# Dash_V2.net
KiCad netlist of a schematic drawn in EAGLE
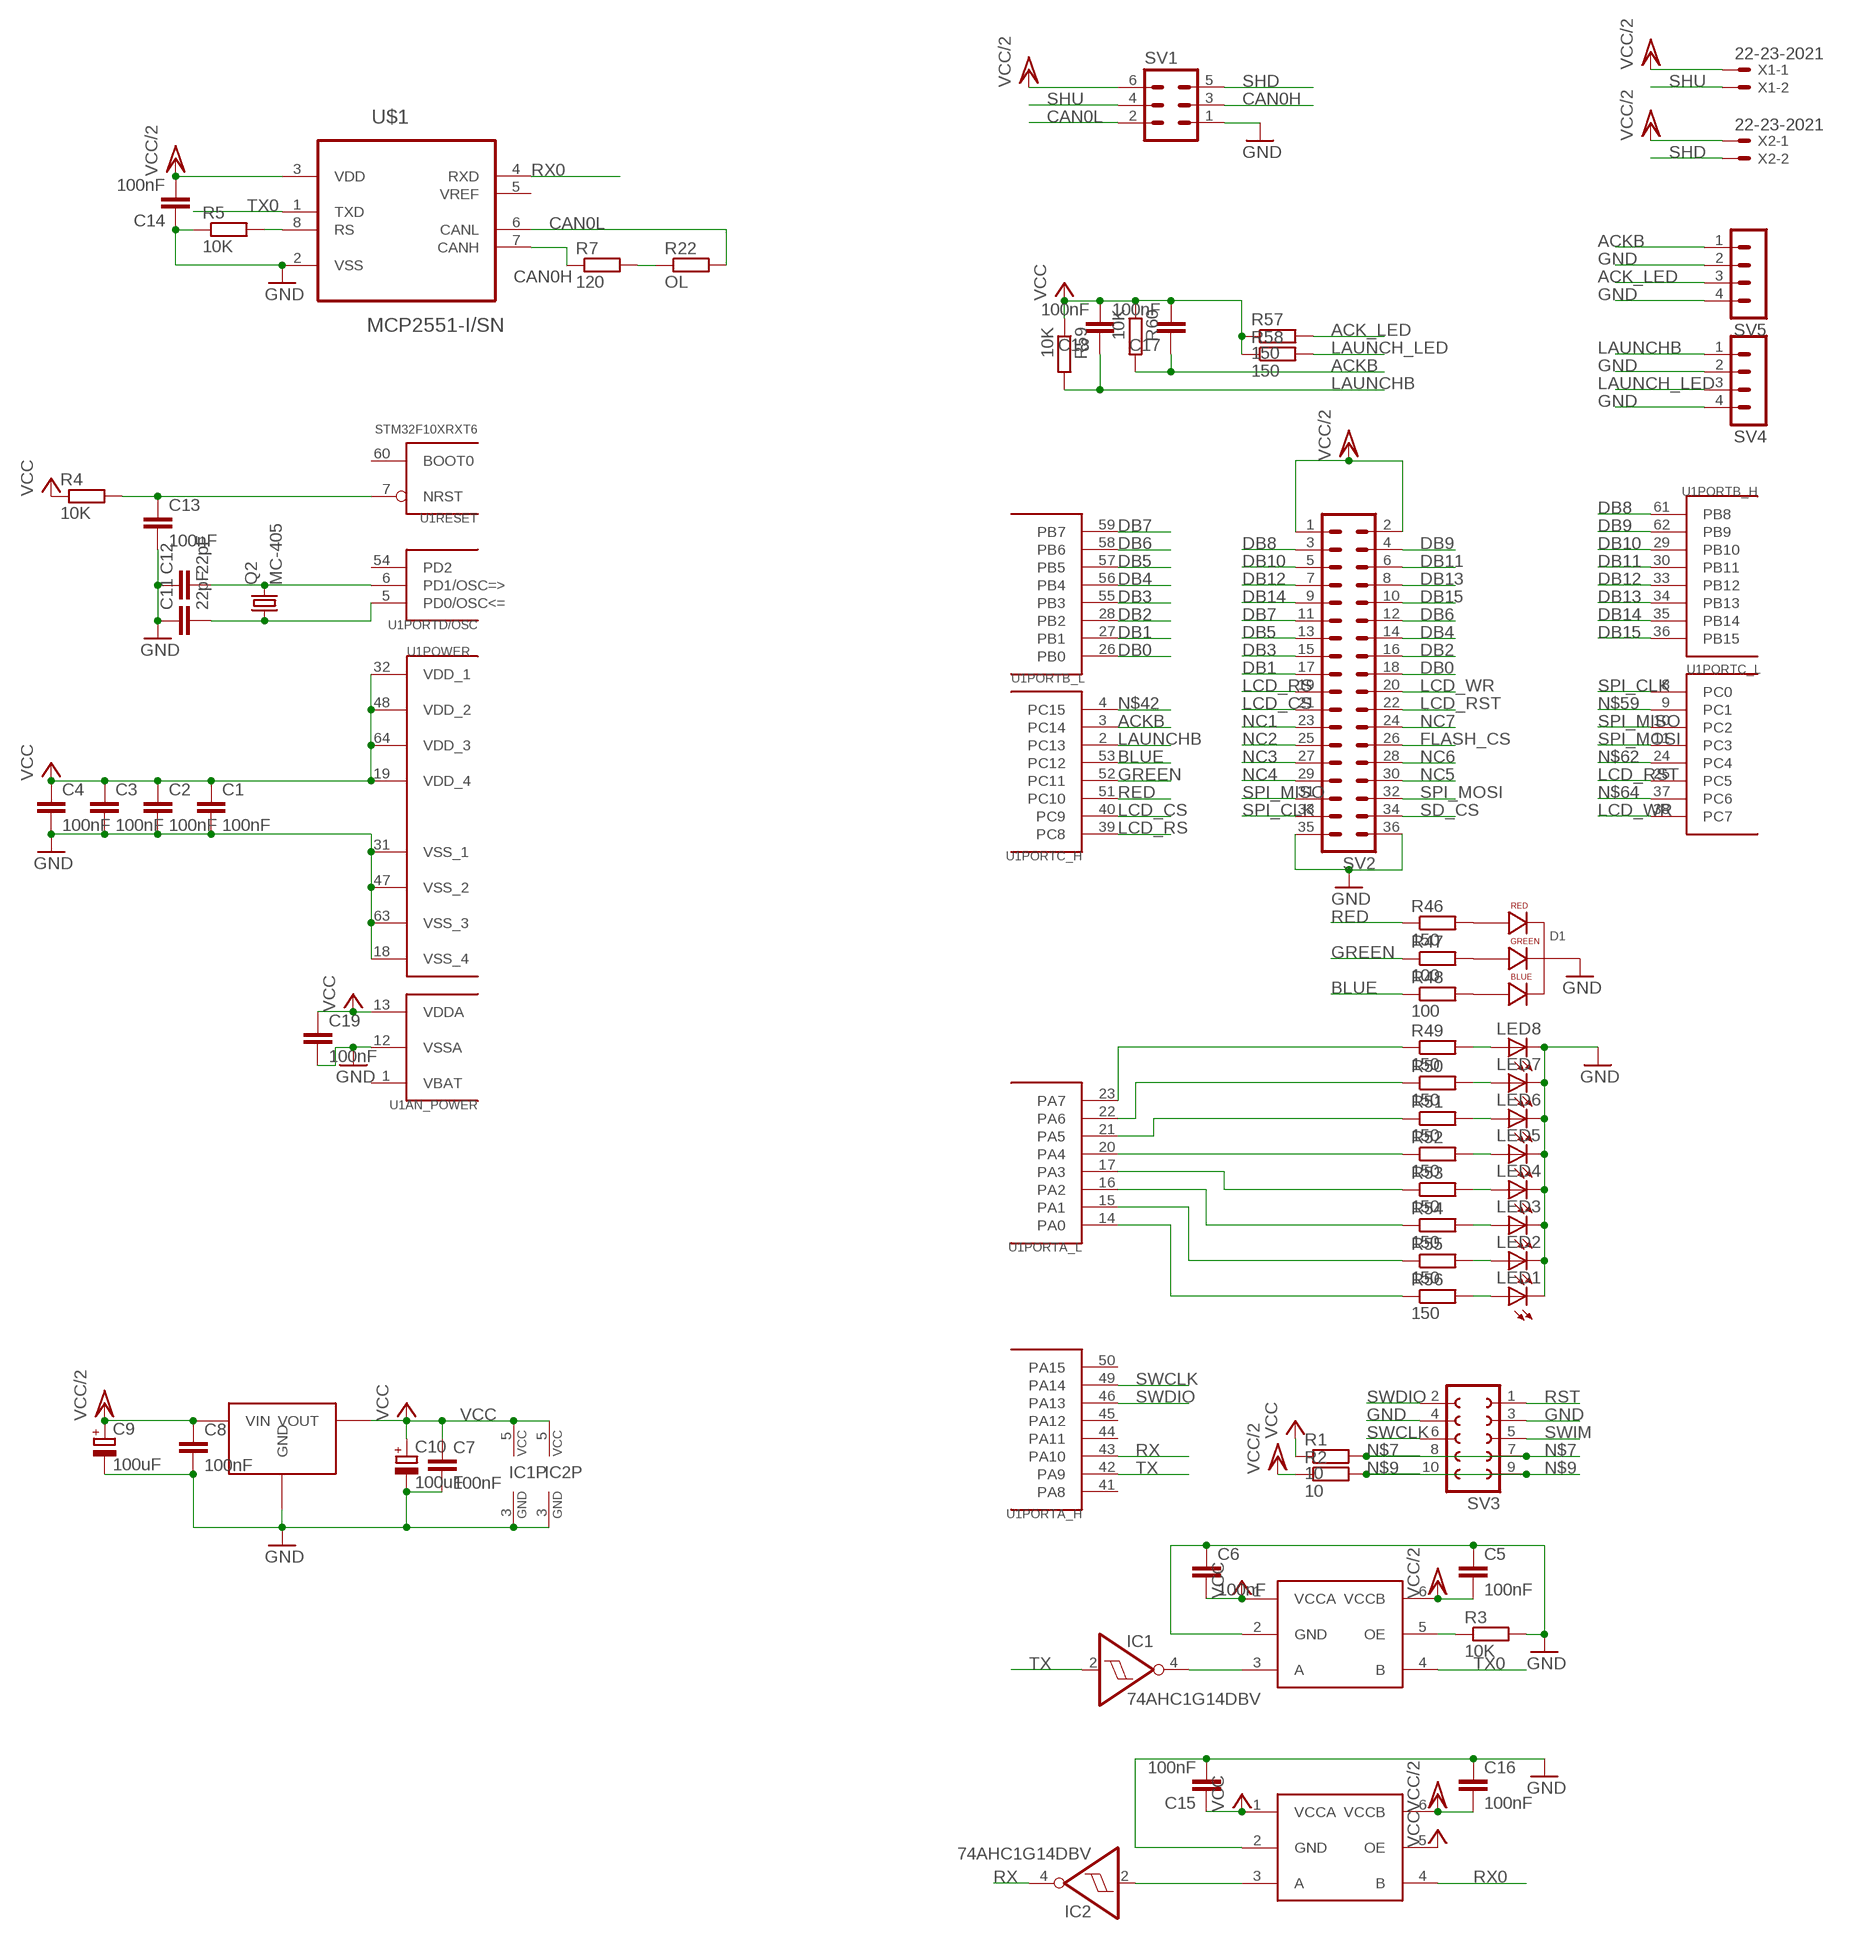
[diagram p0: schematic, sheet 1]

(export (version "E")
  (design (tool "Eeschema 10.0.6"))
  (components
    (comp (ref "C1")
      (value "100nF")
      (footprint "eagle-import:C0805")
      (libsource (lib "eagle-import") (part "C-EUC0805"))
    )
    (comp (ref "C2")
      (value "100nF")
      (footprint "eagle-import:C0805")
      (libsource (lib "eagle-import") (part "C-EUC0805"))
    )
    (comp (ref "C3")
      (value "100nF")
      (footprint "eagle-import:C0805")
      (libsource (lib "eagle-import") (part "C-EUC0805"))
    )
    (comp (ref "C4")
      (value "100nF")
      (footprint "eagle-import:C0805")
      (libsource (lib "eagle-import") (part "C-EUC0805"))
    )
    (comp (ref "C5")
      (value "100nF")
      (footprint "eagle-import:C0805")
      (libsource (lib "eagle-import") (part "C-EUC0805"))
    )
    (comp (ref "C6")
      (value "100nF")
      (footprint "eagle-import:C0805")
      (libsource (lib "eagle-import") (part "C-EUC0805"))
    )
    (comp (ref "C7")
      (value "100nF")
      (footprint "eagle-import:C0805")
      (libsource (lib "eagle-import") (part "C-EUC0805"))
    )
    (comp (ref "C8")
      (value "100nF")
      (footprint "eagle-import:C0805")
      (libsource (lib "eagle-import") (part "C-EUC0805"))
    )
    (comp (ref "C9")
      (value "100uF")
      (footprint "eagle-import:153CLV-0605")
      (libsource (lib "eagle-import") (part "CPOL-EU153CLV-0605"))
    )
    (comp (ref "C10")
      (value "100uF")
      (footprint "eagle-import:153CLV-0605")
      (libsource (lib "eagle-import") (part "CPOL-EU153CLV-0605"))
    )
    (comp (ref "C11")
      (value "22pF")
      (footprint "eagle-import:C0805")
      (libsource (lib "eagle-import") (part "C-EUC0805"))
    )
    (comp (ref "C12")
      (value "22pF")
      (footprint "eagle-import:C0805")
      (libsource (lib "eagle-import") (part "C-EUC0805"))
    )
    (comp (ref "C13")
      (value "100nF")
      (footprint "eagle-import:C0805")
      (libsource (lib "eagle-import") (part "C-EUC0805"))
    )
    (comp (ref "C14")
      (value "100nF")
      (footprint "eagle-import:C0805")
      (libsource (lib "eagle-import") (part "C-EUC0805"))
    )
    (comp (ref "C15")
      (value "100nF")
      (footprint "eagle-import:C0805")
      (libsource (lib "eagle-import") (part "C-EUC0805"))
    )
    (comp (ref "C16")
      (value "100nF")
      (footprint "eagle-import:C0805")
      (libsource (lib "eagle-import") (part "C-EUC0805"))
    )
    (comp (ref "C17")
      (value "100nF")
      (footprint "eagle-import:C0805")
      (libsource (lib "eagle-import") (part "C-EUC0805"))
    )
    (comp (ref "C18")
      (value "100nF")
      (footprint "eagle-import:C0805")
      (libsource (lib "eagle-import") (part "C-EUC0805"))
    )
    (comp (ref "C19")
      (value "100nF")
      (footprint "eagle-import:C0805")
      (libsource (lib "eagle-import") (part "C-EUC0805"))
    )
    (comp (ref "D1")
      (value "LED-RGB-CC-THRUDIFFUSE")
      (footprint "eagle-import:LED-RGB-THRU")
      (libsource (lib "eagle-import") (part "LED-RGB-CC-THRUDIFFUSE"))
    )
    (comp (ref "IC1")
      (value "74AHC1G14DBV")
      (footprint "eagle-import:SOT23-5")
      (fields (field (name "FARNELL") "1893832"))
      (libsource (lib "eagle-import") (part "741G14DBVAHC"))
    )
    (comp (ref "IC2")
      (value "74AHC1G14DBV")
      (footprint "eagle-import:SOT23-5")
      (fields (field (name "FARNELL") "1893832"))
      (libsource (lib "eagle-import") (part "741G14DBVAHC"))
    )
    (comp (ref "LED1")
      (value "LED5MM")
      (footprint "eagle-import:LED5MM")
      (libsource (lib "eagle-import") (part "LED5MM"))
    )
    (comp (ref "LED2")
      (value "LED5MM")
      (footprint "eagle-import:LED5MM")
      (libsource (lib "eagle-import") (part "LED5MM"))
    )
    (comp (ref "LED3")
      (value "LED5MM")
      (footprint "eagle-import:LED5MM")
      (libsource (lib "eagle-import") (part "LED5MM"))
    )
    (comp (ref "LED4")
      (value "LED5MM")
      (footprint "eagle-import:LED5MM")
      (libsource (lib "eagle-import") (part "LED5MM"))
    )
    (comp (ref "LED5")
      (value "LED5MM")
      (footprint "eagle-import:LED5MM")
      (libsource (lib "eagle-import") (part "LED5MM"))
    )
    (comp (ref "LED6")
      (value "LED5MM")
      (footprint "eagle-import:LED5MM")
      (libsource (lib "eagle-import") (part "LED5MM"))
    )
    (comp (ref "LED7")
      (value "LED5MM")
      (footprint "eagle-import:LED5MM")
      (libsource (lib "eagle-import") (part "LED5MM"))
    )
    (comp (ref "LED8")
      (value "LED5MM")
      (footprint "eagle-import:LED5MM")
      (libsource (lib "eagle-import") (part "LED5MM"))
    )
    (comp (ref "Q2")
      (value "MC-405")
      (footprint "eagle-import:MC-405")
      (fields (field (name "OC_FARNELL") "2101329"))
      (libsource (lib "eagle-import") (part "MC-405"))
    )
    (comp (ref "R1")
      (value "10")
      (footprint "eagle-import:R0805")
      (libsource (lib "eagle-import") (part "R-EU_R0805"))
    )
    (comp (ref "R2")
      (value "10")
      (footprint "eagle-import:R0805")
      (libsource (lib "eagle-import") (part "R-EU_R0805"))
    )
    (comp (ref "R3")
      (value "10K")
      (footprint "eagle-import:R1206")
      (libsource (lib "eagle-import") (part "R-EU_R1206"))
    )
    (comp (ref "R4")
      (value "10K")
      (footprint "eagle-import:R0805")
      (libsource (lib "eagle-import") (part "R-EU_R0805"))
    )
    (comp (ref "R5")
      (value "10K")
      (footprint "eagle-import:R0805")
      (libsource (lib "eagle-import") (part "R-EU_R0805"))
    )
    (comp (ref "R7")
      (value "120")
      (footprint "eagle-import:R0805")
      (libsource (lib "eagle-import") (part "R-EU_R0805"))
    )
    (comp (ref "R22")
      (value "OL")
      (footprint "eagle-import:R0805")
      (libsource (lib "eagle-import") (part "R-EU_R0805"))
    )
    (comp (ref "R46")
      (value "150")
      (footprint "eagle-import:R1206")
      (libsource (lib "eagle-import") (part "R-EU_R1206"))
    )
    (comp (ref "R47")
      (value "100")
      (footprint "eagle-import:R1206")
      (libsource (lib "eagle-import") (part "R-EU_R1206"))
    )
    (comp (ref "R48")
      (value "100")
      (footprint "eagle-import:R1206")
      (libsource (lib "eagle-import") (part "R-EU_R1206"))
    )
    (comp (ref "R49")
      (value "150")
      (footprint "eagle-import:R1206")
      (libsource (lib "eagle-import") (part "R-EU_R1206"))
    )
    (comp (ref "R50")
      (value "150")
      (footprint "eagle-import:R1206")
      (libsource (lib "eagle-import") (part "R-EU_R1206"))
    )
    (comp (ref "R51")
      (value "150")
      (footprint "eagle-import:R1206")
      (libsource (lib "eagle-import") (part "R-EU_R1206"))
    )
    (comp (ref "R52")
      (value "150")
      (footprint "eagle-import:R1206")
      (libsource (lib "eagle-import") (part "R-EU_R1206"))
    )
    (comp (ref "R53")
      (value "150")
      (footprint "eagle-import:R1206")
      (libsource (lib "eagle-import") (part "R-EU_R1206"))
    )
    (comp (ref "R54")
      (value "150")
      (footprint "eagle-import:R1206")
      (libsource (lib "eagle-import") (part "R-EU_R1206"))
    )
    (comp (ref "R55")
      (value "150")
      (footprint "eagle-import:R1206")
      (libsource (lib "eagle-import") (part "R-EU_R1206"))
    )
    (comp (ref "R56")
      (value "150")
      (footprint "eagle-import:R1206")
      (libsource (lib "eagle-import") (part "R-EU_R1206"))
    )
    (comp (ref "R57")
      (value "150")
      (footprint "eagle-import:R1206")
      (libsource (lib "eagle-import") (part "R-EU_R1206"))
    )
    (comp (ref "R58")
      (value "150")
      (footprint "eagle-import:R1206")
      (libsource (lib "eagle-import") (part "R-EU_R1206"))
    )
    (comp (ref "R59")
      (value "10K")
      (footprint "eagle-import:R1206")
      (libsource (lib "eagle-import") (part "R-EU_R1206"))
    )
    (comp (ref "R60")
      (value "10K")
      (footprint "eagle-import:R1206")
      (libsource (lib "eagle-import") (part "R-EU_R1206"))
    )
    (comp (ref "SV1")
      (value "MA03-2")
      (footprint "eagle-import:MA03-2")
      (libsource (lib "eagle-import") (part "MA03-2"))
    )
    (comp (ref "SV2")
      (value "MA18-2")
      (footprint "eagle-import:MA18-2")
      (libsource (lib "eagle-import") (part "MA18-2"))
    )
    (comp (ref "SV3")
      (value "FE05-2W")
      (footprint "eagle-import:FE05-2W")
      (libsource (lib "eagle-import") (part "FE05-2W"))
    )
    (comp (ref "SV4")
      (value "MA04-1")
      (footprint "eagle-import:MA04-1")
      (libsource (lib "eagle-import") (part "MA04-1"))
    )
    (comp (ref "SV5")
      (value "MA04-1")
      (footprint "eagle-import:MA04-1")
      (libsource (lib "eagle-import") (part "MA04-1"))
    )
    (comp (ref "U$1")
      (value "MCP2551-I/SN")
      (footprint "eagle-import:SOIC127P600X175-8N")
      (libsource (lib "eagle-import") (part "MCP2551-I/SN"))
    )
    (comp (ref "U$2")
      (value "TXB0101")
      (footprint "eagle-import:TSOT23-6_DDC")
      (libsource (lib "eagle-import") (part "TXB0101"))
    )
    (comp (ref "U$3")
      (value "TS2940")
      (footprint "eagle-import:TO-252")
      (libsource (lib "eagle-import") (part "TS2940"))
    )
    (comp (ref "U$4")
      (value "TXB0101")
      (footprint "eagle-import:TSOT23-6_DDC")
      (libsource (lib "eagle-import") (part "TXB0101"))
    )
    (comp (ref "U1")
      (value "STM32F10XRXT6")
      (footprint "eagle-import:TQFP64")
      (libsource (lib "eagle-import") (part "STM32F10XRXT6"))
    )
    (comp (ref "X1")
      (value "22-23-2021")
      (footprint "eagle-import:22-23-2021")
      (fields (field (name "MF") "MOLEX"))
      (libsource (lib "eagle-import") (part "22-23-2021"))
    )
    (comp (ref "X2")
      (value "22-23-2021")
      (footprint "eagle-import:22-23-2021")
      (fields (field (name "MF") "MOLEX"))
      (libsource (lib "eagle-import") (part "22-23-2021"))
    )
  )
  (nets
    (net (code "1") (name "/ACKB") (class "Default")
      (node (ref "C17") (pin "1") (pinfunction "1_1") (pintype "passive"))
      (node (ref "R60") (pin "2") (pinfunction "2_2") (pintype "passive"))
      (node (ref "SV5") (pin "1") (pinfunction "1_1") (pintype "passive"))
      (node (ref "U1") (pin "3") (pinfunction "PC14_3") (pintype "bidirectional"))
    )
    (net (code "2") (name "/ACK_LED") (class "Default")
      (node (ref "R57") (pin "2") (pinfunction "2_2") (pintype "passive"))
      (node (ref "SV5") (pin "3") (pinfunction "3_3") (pintype "passive"))
    )
    (net (code "3") (name "/BLUE") (class "Default")
      (node (ref "R48") (pin "1") (pinfunction "1_1") (pintype "passive"))
      (node (ref "U1") (pin "53") (pinfunction "PC12_53") (pintype "bidirectional"))
    )
    (net (code "4") (name "/CAN0H") (class "Default")
      (node (ref "R7") (pin "1") (pinfunction "1_1") (pintype "passive"))
      (node (ref "SV1") (pin "3") (pinfunction "3_3") (pintype "passive"))
      (node (ref "U$1") (pin "7") (pinfunction "CANH_7") (pintype "bidirectional"))
    )
    (net (code "5") (name "/CAN0L") (class "Default")
      (node (ref "R22") (pin "2") (pinfunction "2_2") (pintype "passive"))
      (node (ref "SV1") (pin "2") (pinfunction "2_2") (pintype "passive"))
      (node (ref "U$1") (pin "6") (pinfunction "CANL_6") (pintype "bidirectional"))
    )
    (net (code "6") (name "/DB0") (class "Default")
      (node (ref "SV2") (pin "18") (pinfunction "18_18") (pintype "passive"))
      (node (ref "U1") (pin "26") (pinfunction "PB0_26") (pintype "bidirectional"))
    )
    (net (code "7") (name "/DB1") (class "Default")
      (node (ref "SV2") (pin "17") (pinfunction "17_17") (pintype "passive"))
      (node (ref "U1") (pin "27") (pinfunction "PB1_27") (pintype "bidirectional"))
    )
    (net (code "8") (name "/DB2") (class "Default")
      (node (ref "SV2") (pin "16") (pinfunction "16_16") (pintype "passive"))
      (node (ref "U1") (pin "28") (pinfunction "PB2_28") (pintype "bidirectional"))
    )
    (net (code "9") (name "/DB3") (class "Default")
      (node (ref "SV2") (pin "15") (pinfunction "15_15") (pintype "passive"))
      (node (ref "U1") (pin "55") (pinfunction "PB3_55") (pintype "bidirectional"))
    )
    (net (code "10") (name "/DB4") (class "Default")
      (node (ref "SV2") (pin "14") (pinfunction "14_14") (pintype "passive"))
      (node (ref "U1") (pin "56") (pinfunction "PB4_56") (pintype "bidirectional"))
    )
    (net (code "11") (name "/DB5") (class "Default")
      (node (ref "SV2") (pin "13") (pinfunction "13_13") (pintype "passive"))
      (node (ref "U1") (pin "57") (pinfunction "PB5_57") (pintype "bidirectional"))
    )
    (net (code "12") (name "/DB6") (class "Default")
      (node (ref "SV2") (pin "12") (pinfunction "12_12") (pintype "passive"))
      (node (ref "U1") (pin "58") (pinfunction "PB6_58") (pintype "bidirectional"))
    )
    (net (code "13") (name "/DB7") (class "Default")
      (node (ref "SV2") (pin "11") (pinfunction "11_11") (pintype "passive"))
      (node (ref "U1") (pin "59") (pinfunction "PB7_59") (pintype "bidirectional"))
    )
    (net (code "14") (name "/DB8") (class "Default")
      (node (ref "SV2") (pin "3") (pinfunction "3_3") (pintype "passive"))
      (node (ref "U1") (pin "61") (pinfunction "PB8_61") (pintype "bidirectional"))
    )
    (net (code "15") (name "/DB9") (class "Default")
      (node (ref "SV2") (pin "4") (pinfunction "4_4") (pintype "passive"))
      (node (ref "U1") (pin "62") (pinfunction "PB9_62") (pintype "bidirectional"))
    )
    (net (code "16") (name "/DB10") (class "Default")
      (node (ref "SV2") (pin "5") (pinfunction "5_5") (pintype "passive"))
      (node (ref "U1") (pin "29") (pinfunction "PB10_29") (pintype "bidirectional"))
    )
    (net (code "17") (name "/DB11") (class "Default")
      (node (ref "SV2") (pin "6") (pinfunction "6_6") (pintype "passive"))
      (node (ref "U1") (pin "30") (pinfunction "PB11_30") (pintype "bidirectional"))
    )
    (net (code "18") (name "/DB12") (class "Default")
      (node (ref "SV2") (pin "7") (pinfunction "7_7") (pintype "passive"))
      (node (ref "U1") (pin "33") (pinfunction "PB12_33") (pintype "bidirectional"))
    )
    (net (code "19") (name "/DB13") (class "Default")
      (node (ref "SV2") (pin "8") (pinfunction "8_8") (pintype "passive"))
      (node (ref "U1") (pin "34") (pinfunction "PB13_34") (pintype "bidirectional"))
    )
    (net (code "20") (name "/DB14") (class "Default")
      (node (ref "SV2") (pin "9") (pinfunction "9_9") (pintype "passive"))
      (node (ref "U1") (pin "35") (pinfunction "PB14_35") (pintype "bidirectional"))
    )
    (net (code "21") (name "/DB15") (class "Default")
      (node (ref "SV2") (pin "10") (pinfunction "10_10") (pintype "passive"))
      (node (ref "U1") (pin "36") (pinfunction "PB15_36") (pintype "bidirectional"))
    )
    (net (code "22") (name "/FLASH_CS") (class "Default")
      (node (ref "SV2") (pin "26") (pinfunction "26_26") (pintype "passive"))
    )
    (net (code "23") (name "/GREEN") (class "Default")
      (node (ref "R47") (pin "1") (pinfunction "1_1") (pintype "passive"))
      (node (ref "U1") (pin "52") (pinfunction "PC11_52") (pintype "bidirectional"))
    )
    (net (code "24") (name "/LAUNCHB") (class "Default")
      (node (ref "C18") (pin "1") (pinfunction "1_1") (pintype "passive"))
      (node (ref "R59") (pin "2") (pinfunction "2_2") (pintype "passive"))
      (node (ref "SV4") (pin "1") (pinfunction "1_1") (pintype "passive"))
      (node (ref "U1") (pin "2") (pinfunction "PC13_2") (pintype "bidirectional"))
    )
    (net (code "25") (name "/LAUNCH_LED") (class "Default")
      (node (ref "R58") (pin "2") (pinfunction "2_2") (pintype "passive"))
      (node (ref "SV4") (pin "3") (pinfunction "3_3") (pintype "passive"))
    )
    (net (code "26") (name "/LCD_CS") (class "Default")
      (node (ref "SV2") (pin "21") (pinfunction "21_21") (pintype "passive"))
      (node (ref "U1") (pin "40") (pinfunction "PC9_40") (pintype "bidirectional"))
    )
    (net (code "27") (name "/LCD_RS") (class "Default")
      (node (ref "SV2") (pin "19") (pinfunction "19_19") (pintype "passive"))
      (node (ref "U1") (pin "39") (pinfunction "PC8_39") (pintype "bidirectional"))
    )
    (net (code "28") (name "/LCD_RST") (class "Default")
      (node (ref "SV2") (pin "22") (pinfunction "22_22") (pintype "passive"))
      (node (ref "U1") (pin "25") (pinfunction "PC5_25") (pintype "bidirectional"))
    )
    (net (code "29") (name "/LCD_WR") (class "Default")
      (node (ref "SV2") (pin "20") (pinfunction "20_20") (pintype "passive"))
      (node (ref "U1") (pin "38") (pinfunction "PC7_38") (pintype "bidirectional"))
    )
    (net (code "30") (name "/N$7") (class "Default")
      (node (ref "R1") (pin "2") (pinfunction "2_2") (pintype "passive"))
      (node (ref "SV3") (pin "7") (pinfunction "7_7") (pintype "passive"))
      (node (ref "SV3") (pin "8") (pinfunction "8_8") (pintype "passive"))
    )
    (net (code "31") (name "/N$9") (class "Default")
      (node (ref "R2") (pin "2") (pinfunction "2_2") (pintype "passive"))
      (node (ref "SV3") (pin "10") (pinfunction "10_10") (pintype "passive"))
      (node (ref "SV3") (pin "9") (pinfunction "9_9") (pintype "passive"))
    )
    (net (code "32") (name "/N$42") (class "Default")
      (node (ref "U1") (pin "4") (pinfunction "PC15_4") (pintype "bidirectional"))
    )
    (net (code "33") (name "/N$59") (class "Default")
      (node (ref "U1") (pin "9") (pinfunction "PC1_9") (pintype "bidirectional"))
    )
    (net (code "34") (name "/N$62") (class "Default")
      (node (ref "U1") (pin "24") (pinfunction "PC4_24") (pintype "bidirectional"))
    )
    (net (code "35") (name "/N$64") (class "Default")
      (node (ref "U1") (pin "37") (pinfunction "PC6_37") (pintype "bidirectional"))
    )
    (net (code "36") (name "/NC1") (class "Default")
      (node (ref "SV2") (pin "23") (pinfunction "23_23") (pintype "passive"))
    )
    (net (code "37") (name "/NC2") (class "Default")
      (node (ref "SV2") (pin "25") (pinfunction "25_25") (pintype "passive"))
    )
    (net (code "38") (name "/NC3") (class "Default")
      (node (ref "SV2") (pin "27") (pinfunction "27_27") (pintype "passive"))
    )
    (net (code "39") (name "/NC4") (class "Default")
      (node (ref "SV2") (pin "29") (pinfunction "29_29") (pintype "passive"))
    )
    (net (code "40") (name "/NC5") (class "Default")
      (node (ref "SV2") (pin "30") (pinfunction "30_30") (pintype "passive"))
    )
    (net (code "41") (name "/NC6") (class "Default")
      (node (ref "SV2") (pin "28") (pinfunction "28_28") (pintype "passive"))
    )
    (net (code "42") (name "/NC7") (class "Default")
      (node (ref "SV2") (pin "24") (pinfunction "24_24") (pintype "passive"))
    )
    (net (code "43") (name "/RED") (class "Default")
      (node (ref "R46") (pin "1") (pinfunction "1_1") (pintype "passive"))
      (node (ref "U1") (pin "51") (pinfunction "PC10_51") (pintype "bidirectional"))
    )
    (net (code "44") (name "/RST") (class "Default")
      (node (ref "C13") (pin "1") (pinfunction "1_1") (pintype "passive"))
      (node (ref "R4") (pin "2") (pinfunction "2_2") (pintype "passive"))
      (node (ref "SV3") (pin "1") (pinfunction "1_1") (pintype "passive"))
      (node (ref "U1") (pin "7") (pinfunction "NRST_7") (pintype "input"))
    )
    (net (code "45") (name "/RX") (class "Default")
      (node (ref "IC2") (pin "4") (pinfunction "O_4") (pintype "output"))
      (node (ref "U1") (pin "43") (pinfunction "PA10_43") (pintype "bidirectional"))
    )
    (net (code "46") (name "/RX0") (class "Default")
      (node (ref "U$1") (pin "4") (pinfunction "RXD_4") (pintype "output"))
      (node (ref "U$4") (pin "4") (pinfunction "B_4") (pintype "bidirectional"))
    )
    (net (code "47") (name "/SD_CS") (class "Default")
      (node (ref "SV2") (pin "34") (pinfunction "34_34") (pintype "passive"))
    )
    (net (code "48") (name "/SHD") (class "Default")
      (node (ref "SV1") (pin "5") (pinfunction "5_5") (pintype "passive"))
      (node (ref "X2") (pin "2") (pinfunction "S_2") (pintype "passive"))
    )
    (net (code "49") (name "/SHU") (class "Default")
      (node (ref "SV1") (pin "4") (pinfunction "4_4") (pintype "passive"))
      (node (ref "X1") (pin "2") (pinfunction "S_2") (pintype "passive"))
    )
    (net (code "50") (name "/SPI_CLK") (class "Default")
      (node (ref "SV2") (pin "33") (pinfunction "33_33") (pintype "passive"))
      (node (ref "U1") (pin "8") (pinfunction "PC0_8") (pintype "bidirectional"))
    )
    (net (code "51") (name "/SPI_MISO") (class "Default")
      (node (ref "SV2") (pin "31") (pinfunction "31_31") (pintype "passive"))
      (node (ref "U1") (pin "10") (pinfunction "PC2_10") (pintype "bidirectional"))
    )
    (net (code "52") (name "/SPI_MOSI") (class "Default")
      (node (ref "SV2") (pin "32") (pinfunction "32_32") (pintype "passive"))
      (node (ref "U1") (pin "11") (pinfunction "PC3_11") (pintype "bidirectional"))
    )
    (net (code "53") (name "/SWCLK") (class "Default")
      (node (ref "SV3") (pin "6") (pinfunction "6_6") (pintype "passive"))
      (node (ref "U1") (pin "49") (pinfunction "PA14_49") (pintype "bidirectional"))
    )
    (net (code "54") (name "/SWDIO") (class "Default")
      (node (ref "SV3") (pin "2") (pinfunction "2_2") (pintype "passive"))
      (node (ref "U1") (pin "46") (pinfunction "PA13_46") (pintype "bidirectional"))
    )
    (net (code "55") (name "/SWIM") (class "Default")
      (node (ref "SV3") (pin "5") (pinfunction "5_5") (pintype "passive"))
    )
    (net (code "56") (name "/TX") (class "Default")
      (node (ref "IC1") (pin "2") (pinfunction "I_2") (pintype "input"))
      (node (ref "U1") (pin "42") (pinfunction "PA9_42") (pintype "bidirectional"))
    )
    (net (code "57") (name "/TX0") (class "Default")
      (node (ref "U$1") (pin "1") (pinfunction "TXD_1") (pintype "input"))
      (node (ref "U$2") (pin "4") (pinfunction "B_4") (pintype "bidirectional"))
    )
    (net (code "58") (name "/VBAT") (class "Default")
      (node (ref "U1") (pin "1") (pinfunction "VBAT_1") (pintype "power_in"))
    )
    (net (code "59") (name "GND") (class "Default")
      (node (ref "C1") (pin "2") (pinfunction "2_2") (pintype "passive"))
      (node (ref "C10") (pin "-") (pinfunction "-_-") (pintype "passive"))
      (node (ref "C11") (pin "1") (pinfunction "1_1") (pintype "passive"))
      (node (ref "C12") (pin "1") (pinfunction "1_1") (pintype "passive"))
      (node (ref "C13") (pin "2") (pinfunction "2_2") (pintype "passive"))
      (node (ref "C14") (pin "1") (pinfunction "1_1") (pintype "passive"))
      (node (ref "C15") (pin "2") (pinfunction "2_2") (pintype "passive"))
      (node (ref "C16") (pin "1") (pinfunction "1_1") (pintype "passive"))
      (node (ref "C19") (pin "2") (pinfunction "2_2") (pintype "passive"))
      (node (ref "C2") (pin "2") (pinfunction "2_2") (pintype "passive"))
      (node (ref "C3") (pin "2") (pinfunction "2_2") (pintype "passive"))
      (node (ref "C4") (pin "2") (pinfunction "2_2") (pintype "passive"))
      (node (ref "C5") (pin "1") (pinfunction "1_1") (pintype "passive"))
      (node (ref "C6") (pin "1") (pinfunction "1_1") (pintype "passive"))
      (node (ref "C7") (pin "2") (pinfunction "2_2") (pintype "passive"))
      (node (ref "C8") (pin "2") (pinfunction "2_2") (pintype "passive"))
      (node (ref "C9") (pin "-") (pinfunction "-_-") (pintype "passive"))
      (node (ref "D1") (pin "2") (pinfunction "CATHODE_2") (pintype "bidirectional"))
      (node (ref "IC1") (pin "3") (pinfunction "GND_3") (pintype "power_in"))
      (node (ref "IC2") (pin "3") (pinfunction "GND_3") (pintype "power_in"))
      (node (ref "LED1") (pin "K") (pinfunction "C_K") (pintype "passive"))
      (node (ref "LED2") (pin "K") (pinfunction "C_K") (pintype "passive"))
      (node (ref "LED3") (pin "K") (pinfunction "C_K") (pintype "passive"))
      (node (ref "LED4") (pin "K") (pinfunction "C_K") (pintype "passive"))
      (node (ref "LED5") (pin "K") (pinfunction "C_K") (pintype "passive"))
      (node (ref "LED6") (pin "K") (pinfunction "C_K") (pintype "passive"))
      (node (ref "LED7") (pin "K") (pinfunction "C_K") (pintype "passive"))
      (node (ref "LED8") (pin "K") (pinfunction "C_K") (pintype "passive"))
      (node (ref "R3") (pin "2") (pinfunction "2_2") (pintype "passive"))
      (node (ref "R5") (pin "1") (pinfunction "1_1") (pintype "passive"))
      (node (ref "SV1") (pin "1") (pinfunction "1_1") (pintype "passive"))
      (node (ref "SV2") (pin "35") (pinfunction "35_35") (pintype "passive"))
      (node (ref "SV2") (pin "36") (pinfunction "36_36") (pintype "passive"))
      (node (ref "SV3") (pin "3") (pinfunction "3_3") (pintype "passive"))
      (node (ref "SV3") (pin "4") (pinfunction "4_4") (pintype "passive"))
      (node (ref "SV4") (pin "2") (pinfunction "2_2") (pintype "passive"))
      (node (ref "SV4") (pin "4") (pinfunction "4_4") (pintype "passive"))
      (node (ref "SV5") (pin "2") (pinfunction "2_2") (pintype "passive"))
      (node (ref "SV5") (pin "4") (pinfunction "4_4") (pintype "passive"))
      (node (ref "U$1") (pin "2") (pinfunction "VSS_2") (pintype "passive"))
      (node (ref "U$2") (pin "2") (pinfunction "GND_2") (pintype "power_in"))
      (node (ref "U$3") (pin "GND") (pinfunction "GND_GND") (pintype "bidirectional"))
      (node (ref "U$4") (pin "2") (pinfunction "GND_2") (pintype "power_in"))
      (node (ref "U1") (pin "12") (pinfunction "VSSA_12") (pintype "power_in"))
      (node (ref "U1") (pin "18") (pinfunction "VSS_4_18") (pintype "power_in"))
      (node (ref "U1") (pin "31") (pinfunction "VSS_1_31") (pintype "power_in"))
      (node (ref "U1") (pin "47") (pinfunction "VSS_2_47") (pintype "power_in"))
      (node (ref "U1") (pin "63") (pinfunction "VSS_3_63") (pintype "power_in"))
    )
    (net (code "60") (name "Net-(D1-BLUE_CATHODE)") (class "Default")
      (node (ref "D1") (pin "4") (pinfunction "BLUE_CATHODE_4") (pintype "bidirectional"))
      (node (ref "R48") (pin "2") (pinfunction "2_2") (pintype "passive"))
    )
    (net (code "61") (name "Net-(D1-GREEN_CATHODE)") (class "Default")
      (node (ref "D1") (pin "3") (pinfunction "GREEN_CATHODE_3") (pintype "bidirectional"))
      (node (ref "R47") (pin "2") (pinfunction "2_2") (pintype "passive"))
    )
    (net (code "62") (name "Net-(D1-RED_CATHODE)") (class "Default")
      (node (ref "D1") (pin "1") (pinfunction "RED_CATHODE_1") (pintype "bidirectional"))
      (node (ref "R46") (pin "2") (pinfunction "2_2") (pintype "passive"))
    )
    (net (code "63") (name "Net-(IC1A-O)") (class "Default")
      (node (ref "IC1") (pin "4") (pinfunction "O_4") (pintype "output"))
      (node (ref "U$2") (pin "3") (pinfunction "A_3") (pintype "bidirectional"))
    )
    (net (code "64") (name "Net-(IC2A-I)") (class "Default")
      (node (ref "IC2") (pin "2") (pinfunction "I_2") (pintype "input"))
      (node (ref "U$4") (pin "3") (pinfunction "A_3") (pintype "bidirectional"))
    )
    (net (code "65") (name "Net-(LED1-PadA)") (class "Default")
      (node (ref "LED1") (pin "A") (pinfunction "A_A") (pintype "passive"))
      (node (ref "R56") (pin "2") (pinfunction "2_2") (pintype "passive"))
    )
    (net (code "66") (name "Net-(LED2-PadA)") (class "Default")
      (node (ref "LED2") (pin "A") (pinfunction "A_A") (pintype "passive"))
      (node (ref "R55") (pin "2") (pinfunction "2_2") (pintype "passive"))
    )
    (net (code "67") (name "Net-(LED3-PadA)") (class "Default")
      (node (ref "LED3") (pin "A") (pinfunction "A_A") (pintype "passive"))
      (node (ref "R54") (pin "2") (pinfunction "2_2") (pintype "passive"))
    )
    (net (code "68") (name "Net-(LED4-PadA)") (class "Default")
      (node (ref "LED4") (pin "A") (pinfunction "A_A") (pintype "passive"))
      (node (ref "R53") (pin "2") (pinfunction "2_2") (pintype "passive"))
    )
    (net (code "69") (name "Net-(LED5-PadA)") (class "Default")
      (node (ref "LED5") (pin "A") (pinfunction "A_A") (pintype "passive"))
      (node (ref "R52") (pin "2") (pinfunction "2_2") (pintype "passive"))
    )
    (net (code "70") (name "Net-(LED6-PadA)") (class "Default")
      (node (ref "LED6") (pin "A") (pinfunction "A_A") (pintype "passive"))
      (node (ref "R51") (pin "2") (pinfunction "2_2") (pintype "passive"))
    )
    (net (code "71") (name "Net-(LED7-PadA)") (class "Default")
      (node (ref "LED7") (pin "A") (pinfunction "A_A") (pintype "passive"))
      (node (ref "R50") (pin "2") (pinfunction "2_2") (pintype "passive"))
    )
    (net (code "72") (name "Net-(LED8-PadA)") (class "Default")
      (node (ref "LED8") (pin "A") (pinfunction "A_A") (pintype "passive"))
      (node (ref "R49") (pin "2") (pinfunction "2_2") (pintype "passive"))
    )
    (net (code "73") (name "Net-(R22-Pad1)") (class "Default")
      (node (ref "R22") (pin "1") (pinfunction "1_1") (pintype "passive"))
      (node (ref "R7") (pin "2") (pinfunction "2_2") (pintype "passive"))
    )
    (net (code "74") (name "Net-(U$1-RS)") (class "Default")
      (node (ref "R5") (pin "2") (pinfunction "2_2") (pintype "passive"))
      (node (ref "U$1") (pin "8") (pinfunction "RS_8") (pintype "input"))
    )
    (net (code "75") (name "Net-(U$2-OE)") (class "Default")
      (node (ref "R3") (pin "1") (pinfunction "1_1") (pintype "passive"))
      (node (ref "U$2") (pin "5") (pinfunction "OE_5") (pintype "bidirectional"))
    )
    (net (code "76") (name "Net-(U1C-PA0)") (class "Default")
      (node (ref "R56") (pin "1") (pinfunction "1_1") (pintype "passive"))
      (node (ref "U1") (pin "14") (pinfunction "PA0_14") (pintype "bidirectional"))
    )
    (net (code "77") (name "Net-(U1C-PA1)") (class "Default")
      (node (ref "R55") (pin "1") (pinfunction "1_1") (pintype "passive"))
      (node (ref "U1") (pin "15") (pinfunction "PA1_15") (pintype "bidirectional"))
    )
    (net (code "78") (name "Net-(U1C-PA2)") (class "Default")
      (node (ref "R54") (pin "1") (pinfunction "1_1") (pintype "passive"))
      (node (ref "U1") (pin "16") (pinfunction "PA2_16") (pintype "bidirectional"))
    )
    (net (code "79") (name "Net-(U1C-PA3)") (class "Default")
      (node (ref "R53") (pin "1") (pinfunction "1_1") (pintype "passive"))
      (node (ref "U1") (pin "17") (pinfunction "PA3_17") (pintype "bidirectional"))
    )
    (net (code "80") (name "Net-(U1C-PA4)") (class "Default")
      (node (ref "R52") (pin "1") (pinfunction "1_1") (pintype "passive"))
      (node (ref "U1") (pin "20") (pinfunction "PA4_20") (pintype "bidirectional"))
    )
    (net (code "81") (name "Net-(U1C-PA5)") (class "Default")
      (node (ref "R51") (pin "1") (pinfunction "1_1") (pintype "passive"))
      (node (ref "U1") (pin "21") (pinfunction "PA5_21") (pintype "bidirectional"))
    )
    (net (code "82") (name "Net-(U1C-PA6)") (class "Default")
      (node (ref "R50") (pin "1") (pinfunction "1_1") (pintype "passive"))
      (node (ref "U1") (pin "22") (pinfunction "PA6_22") (pintype "bidirectional"))
    )
    (net (code "83") (name "Net-(U1C-PA7)") (class "Default")
      (node (ref "R49") (pin "1") (pinfunction "1_1") (pintype "passive"))
      (node (ref "U1") (pin "23") (pinfunction "PA7_23") (pintype "bidirectional"))
    )
    (net (code "84") (name "Net-(U1H-PD0{slash}OSC<=)") (class "Default")
      (node (ref "C11") (pin "2") (pinfunction "2_2") (pintype "passive"))
      (node (ref "Q2") (pin "1") (pinfunction "1_1") (pintype "passive"))
      (node (ref "U1") (pin "5") (pinfunction "PD0/OSC<=_5") (pintype "bidirectional"))
    )
    (net (code "85") (name "Net-(U1H-PD1{slash}OSC=>)") (class "Default")
      (node (ref "C12") (pin "2") (pinfunction "2_2") (pintype "passive"))
      (node (ref "Q2") (pin "2") (pinfunction "2_2") (pintype "passive"))
      (node (ref "U1") (pin "6") (pinfunction "PD1/OSC=>_6") (pintype "bidirectional"))
    )
    (net (code "86") (name "VCC") (class "Default")
      (node (ref "C1") (pin "1") (pinfunction "1_1") (pintype "passive"))
      (node (ref "C10") (pin "+") (pinfunction "+_+") (pintype "passive"))
      (node (ref "C15") (pin "1") (pinfunction "1_1") (pintype "passive"))
      (node (ref "C17") (pin "2") (pinfunction "2_2") (pintype "passive"))
      (node (ref "C18") (pin "2") (pinfunction "2_2") (pintype "passive"))
      (node (ref "C19") (pin "1") (pinfunction "1_1") (pintype "passive"))
      (node (ref "C2") (pin "1") (pinfunction "1_1") (pintype "passive"))
      (node (ref "C3") (pin "1") (pinfunction "1_1") (pintype "passive"))
      (node (ref "C4") (pin "1") (pinfunction "1_1") (pintype "passive"))
      (node (ref "C6") (pin "2") (pinfunction "2_2") (pintype "passive"))
      (node (ref "C7") (pin "1") (pinfunction "1_1") (pintype "passive"))
      (node (ref "IC1") (pin "5") (pinfunction "VCC_5") (pintype "power_in"))
      (node (ref "IC2") (pin "5") (pinfunction "VCC_5") (pintype "power_in"))
      (node (ref "R1") (pin "1") (pinfunction "1_1") (pintype "passive"))
      (node (ref "R4") (pin "1") (pinfunction "1_1") (pintype "passive"))
      (node (ref "R57") (pin "1") (pinfunction "1_1") (pintype "passive"))
      (node (ref "R58") (pin "1") (pinfunction "1_1") (pintype "passive"))
      (node (ref "R59") (pin "1") (pinfunction "1_1") (pintype "passive"))
      (node (ref "R60") (pin "1") (pinfunction "1_1") (pintype "passive"))
      (node (ref "U$2") (pin "1") (pinfunction "VCCA_1") (pintype "power_in"))
      (node (ref "U$3") (pin "VOUT") (pinfunction "VOUT_VOUT") (pintype "bidirectional"))
      (node (ref "U$4") (pin "1") (pinfunction "VCCA_1") (pintype "power_in"))
      (node (ref "U$4") (pin "5") (pinfunction "OE_5") (pintype "bidirectional"))
      (node (ref "U1") (pin "13") (pinfunction "VDDA_13") (pintype "power_in"))
      (node (ref "U1") (pin "19") (pinfunction "VDD_4_19") (pintype "power_in"))
      (node (ref "U1") (pin "32") (pinfunction "VDD_1_32") (pintype "power_in"))
      (node (ref "U1") (pin "48") (pinfunction "VDD_2_48") (pintype "power_in"))
      (node (ref "U1") (pin "64") (pinfunction "VDD_3_64") (pintype "power_in"))
    )
    (net (code "87") (name "VCC{slash}2") (class "Default")
      (node (ref "C14") (pin "2") (pinfunction "2_2") (pintype "passive"))
      (node (ref "C16") (pin "2") (pinfunction "2_2") (pintype "passive"))
      (node (ref "C5") (pin "2") (pinfunction "2_2") (pintype "passive"))
      (node (ref "C8") (pin "1") (pinfunction "1_1") (pintype "passive"))
      (node (ref "C9") (pin "+") (pinfunction "+_+") (pintype "passive"))
      (node (ref "R2") (pin "1") (pinfunction "1_1") (pintype "passive"))
      (node (ref "SV1") (pin "6") (pinfunction "6_6") (pintype "passive"))
      (node (ref "SV2") (pin "1") (pinfunction "1_1") (pintype "passive"))
      (node (ref "SV2") (pin "2") (pinfunction "2_2") (pintype "passive"))
      (node (ref "U$1") (pin "3") (pinfunction "VDD_3") (pintype "power_in"))
      (node (ref "U$2") (pin "6") (pinfunction "VCCB_6") (pintype "power_in"))
      (node (ref "U$3") (pin "VIN") (pinfunction "VIN_VIN") (pintype "bidirectional"))
      (node (ref "U$4") (pin "6") (pinfunction "VCCB_6") (pintype "power_in"))
      (node (ref "X1") (pin "1") (pinfunction "S_1") (pintype "passive"))
      (node (ref "X2") (pin "1") (pinfunction "S_1") (pintype "passive"))
    )
    (net (code "88") (name "unconnected-(U$1-VREF-Pad5)") (class "Default")
      (node (ref "U$1") (pin "5") (pinfunction "VREF_5") (pintype "output"))
    )
    (net (code "89") (name "unconnected-(U1B-PA8-Pad41)") (class "Default")
      (node (ref "U1") (pin "41") (pinfunction "PA8_41") (pintype "bidirectional"))
    )
    (net (code "90") (name "unconnected-(U1B-PA11-Pad44)") (class "Default")
      (node (ref "U1") (pin "44") (pinfunction "PA11_44") (pintype "bidirectional"))
    )
    (net (code "91") (name "unconnected-(U1B-PA12-Pad45)") (class "Default")
      (node (ref "U1") (pin "45") (pinfunction "PA12_45") (pintype "bidirectional"))
    )
    (net (code "92") (name "unconnected-(U1B-PA15-Pad50)") (class "Default")
      (node (ref "U1") (pin "50") (pinfunction "PA15_50") (pintype "bidirectional"))
    )
    (net (code "93") (name "unconnected-(U1H-PD2-Pad54)") (class "Default")
      (node (ref "U1") (pin "54") (pinfunction "PD2_54") (pintype "bidirectional"))
    )
    (net (code "94") (name "unconnected-(U1J-BOOT0-Pad60)") (class "Default")
      (node (ref "U1") (pin "60") (pinfunction "BOOT0_60") (pintype "input"))
    )
  )
)
